# 8_RK3399_SDIO_SPI_GPIOs.net
KiCad netlist of a schematic drawn in Altium Designer
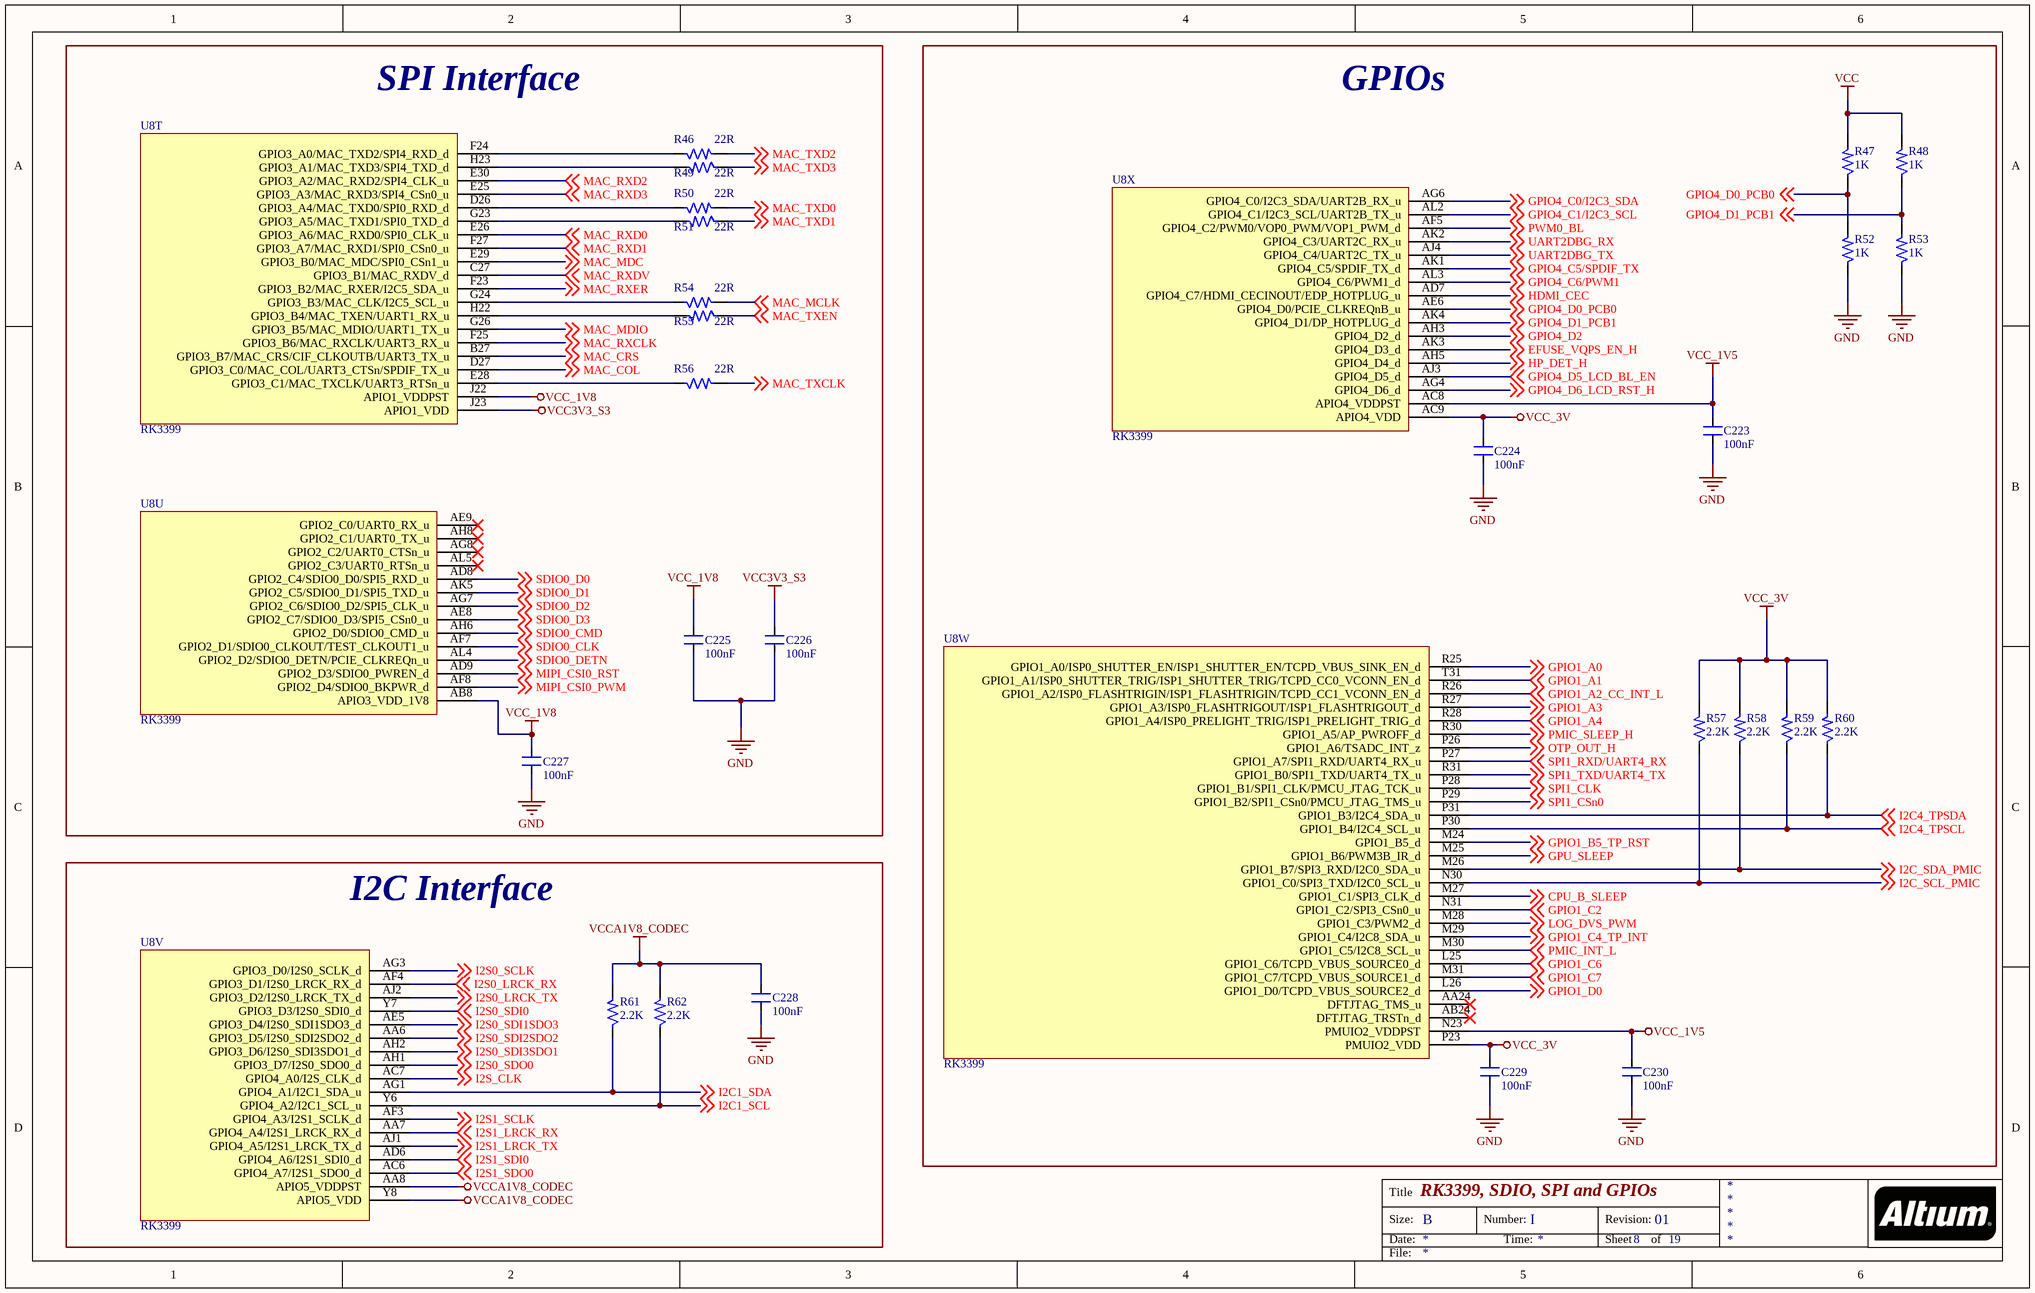
[diagram p0: [8] RK3399_SDIO_SPI_GPIOs.SchDoc]

(export (version "E")
  (design (tool "Eeschema 10.0.6"))
  (components
    (comp (ref "C223")
      (value "100nF")
      (footprint "CAP_0201")
      (description "0.1µF ±10% 25V Ceramic Capacitor X5R 0201 (0603 Metric)")
      (fields
        (field (name "MANUFACTURER") "TDK Corporation")
        (field (name "MANUFACTURER PART NUMBER") "C0603X5R1E104K030BB")
      )
      (libsource (lib "EsteemPCB_SOM_Course_intlib") (part "CAP_100nF-25V-10%-0201"))
    )
    (comp (ref "C224")
      (value "100nF")
      (footprint "CAP_0201")
      (description "0.1µF ±10% 25V Ceramic Capacitor X5R 0201 (0603 Metric)")
      (fields
        (field (name "MANUFACTURER") "TDK Corporation")
        (field (name "MANUFACTURER PART NUMBER") "C0603X5R1E104K030BB")
      )
      (libsource (lib "EsteemPCB_SOM_Course_intlib") (part "CAP_100nF-25V-10%-0201"))
    )
    (comp (ref "C225")
      (value "100nF")
      (footprint "CAP_0201")
      (description "0.1µF ±10% 25V Ceramic Capacitor X5R 0201 (0603 Metric)")
      (fields
        (field (name "MANUFACTURER") "TDK Corporation")
        (field (name "MANUFACTURER PART NUMBER") "C0603X5R1E104K030BB")
      )
      (libsource (lib "EsteemPCB_SOM_Course_intlib") (part "CAP_100nF-25V-10%-0201"))
    )
    (comp (ref "C226")
      (value "100nF")
      (footprint "CAP_0201")
      (description "0.1µF ±10% 25V Ceramic Capacitor X5R 0201 (0603 Metric)")
      (fields
        (field (name "MANUFACTURER") "TDK Corporation")
        (field (name "MANUFACTURER PART NUMBER") "C0603X5R1E104K030BB")
      )
      (libsource (lib "EsteemPCB_SOM_Course_intlib") (part "CAP_100nF-25V-10%-0201"))
    )
    (comp (ref "C227")
      (value "100nF")
      (footprint "CAP_0201")
      (description "0.1µF ±10% 25V Ceramic Capacitor X5R 0201 (0603 Metric)")
      (fields
        (field (name "MANUFACTURER") "TDK Corporation")
        (field (name "MANUFACTURER PART NUMBER") "C0603X5R1E104K030BB")
      )
      (libsource (lib "EsteemPCB_SOM_Course_intlib") (part "CAP_100nF-25V-10%-0201"))
    )
    (comp (ref "C228")
      (value "100nF")
      (footprint "CAP_0201")
      (description "0.1µF ±10% 25V Ceramic Capacitor X5R 0201 (0603 Metric)")
      (fields
        (field (name "MANUFACTURER") "TDK Corporation")
        (field (name "MANUFACTURER PART NUMBER") "C0603X5R1E104K030BB")
      )
      (libsource (lib "EsteemPCB_SOM_Course_intlib") (part "CAP_100nF-25V-10%-0201"))
    )
    (comp (ref "C229")
      (value "100nF")
      (footprint "CAP_0201")
      (description "0.1µF ±10% 25V Ceramic Capacitor X5R 0201 (0603 Metric)")
      (fields
        (field (name "MANUFACTURER") "TDK Corporation")
        (field (name "MANUFACTURER PART NUMBER") "C0603X5R1E104K030BB")
      )
      (libsource (lib "EsteemPCB_SOM_Course_intlib") (part "CAP_100nF-25V-10%-0201"))
    )
    (comp (ref "C230")
      (value "100nF")
      (footprint "CAP_0201")
      (description "0.1µF ±10% 25V Ceramic Capacitor X5R 0201 (0603 Metric)")
      (fields
        (field (name "MANUFACTURER") "TDK Corporation")
        (field (name "MANUFACTURER PART NUMBER") "C0603X5R1E104K030BB")
      )
      (libsource (lib "EsteemPCB_SOM_Course_intlib") (part "CAP_100nF-25V-10%-0201"))
    )
    (comp (ref "R46")
      (value "22R")
      (footprint "RES_0201")
      (description "22 Ohms ±1% 0.05W, 1/20W Chip Resistor 0201 (0603 Metric) Moisture Resistant Thick Film")
      (fields
        (field (name "MANUFACTURER") "Yageo")
        (field (name "MANUFACTURER PART NUMBER") "RC0201FR-0722RL")
      )
      (libsource (lib "EsteemPCB_SOM_Course_intlib") (part "RES_22R-0.05W-1%-0201"))
    )
    (comp (ref "R47")
      (value "1K")
      (footprint "RES_0201")
      (description "1 kOhms ±1% 0.05W, 1/20W Chip Resistor 0201 (0603 Metric) Thick Film")
      (fields
        (field (name "MANUFACTURER") "Yageo")
        (field (name "MANUFACTURER PART NUMBER") "RC0201FR-071KL")
      )
      (libsource (lib "EsteemPCB_SOM_Course_intlib") (part "RES_1K-0.05W-1%-0201"))
    )
    (comp (ref "R48")
      (value "1K")
      (footprint "RES_0201")
      (description "1 kOhms ±1% 0.05W, 1/20W Chip Resistor 0201 (0603 Metric) Thick Film")
      (fields
        (field (name "MANUFACTURER") "Yageo")
        (field (name "MANUFACTURER PART NUMBER") "RC0201FR-071KL")
      )
      (libsource (lib "EsteemPCB_SOM_Course_intlib") (part "RES_1K-0.05W-1%-0201"))
    )
    (comp (ref "R49")
      (value "22R")
      (footprint "RES_0201")
      (description "22 Ohms ±1% 0.05W, 1/20W Chip Resistor 0201 (0603 Metric) Moisture Resistant Thick Film")
      (fields
        (field (name "MANUFACTURER") "Yageo")
        (field (name "MANUFACTURER PART NUMBER") "RC0201FR-0722RL")
      )
      (libsource (lib "EsteemPCB_SOM_Course_intlib") (part "RES_22R-0.05W-1%-0201"))
    )
    (comp (ref "R50")
      (value "22R")
      (footprint "RES_0201")
      (description "22 Ohms ±1% 0.05W, 1/20W Chip Resistor 0201 (0603 Metric) Moisture Resistant Thick Film")
      (fields
        (field (name "MANUFACTURER") "Yageo")
        (field (name "MANUFACTURER PART NUMBER") "RC0201FR-0722RL")
      )
      (libsource (lib "EsteemPCB_SOM_Course_intlib") (part "RES_22R-0.05W-1%-0201"))
    )
    (comp (ref "R51")
      (value "22R")
      (footprint "RES_0201")
      (description "22 Ohms ±1% 0.05W, 1/20W Chip Resistor 0201 (0603 Metric) Moisture Resistant Thick Film")
      (fields
        (field (name "MANUFACTURER") "Yageo")
        (field (name "MANUFACTURER PART NUMBER") "RC0201FR-0722RL")
      )
      (libsource (lib "EsteemPCB_SOM_Course_intlib") (part "RES_22R-0.05W-1%-0201"))
    )
    (comp (ref "R52")
      (value "1K")
      (footprint "RES_0402")
      (description "1 kOhms ±1% 0.1W, 1/10W Chip Resistor 0402 (1005 Metric) Anti-Sulfur Thin Film")
      (fields
        (field (name "MANUFACTURER") "Vishay Beyschlag/Draloric/BC Components")
        (field (name "MANUFACTURER PART NUMBER") "MCS04020C1001FE000")
      )
      (libsource (lib "EsteemPCB_SOM_Course_intlib") (part "RES_1K-0.1W-1%-0402"))
    )
    (comp (ref "R53")
      (value "1K")
      (footprint "RES_0402")
      (description "1 kOhms ±1% 0.1W, 1/10W Chip Resistor 0402 (1005 Metric) Anti-Sulfur Thin Film")
      (fields
        (field (name "MANUFACTURER") "Vishay Beyschlag/Draloric/BC Components")
        (field (name "MANUFACTURER PART NUMBER") "MCS04020C1001FE000")
      )
      (libsource (lib "EsteemPCB_SOM_Course_intlib") (part "RES_1K-0.1W-1%-0402"))
    )
    (comp (ref "R54")
      (value "22R")
      (footprint "RES_0201")
      (description "22 Ohms ±1% 0.05W, 1/20W Chip Resistor 0201 (0603 Metric) Moisture Resistant Thick Film")
      (fields
        (field (name "MANUFACTURER") "Yageo")
        (field (name "MANUFACTURER PART NUMBER") "RC0201FR-0722RL")
      )
      (libsource (lib "EsteemPCB_SOM_Course_intlib") (part "RES_22R-0.05W-1%-0201"))
    )
    (comp (ref "R55")
      (value "22R")
      (footprint "RES_0201")
      (description "22 Ohms ±1% 0.05W, 1/20W Chip Resistor 0201 (0603 Metric) Moisture Resistant Thick Film")
      (fields
        (field (name "MANUFACTURER") "Yageo")
        (field (name "MANUFACTURER PART NUMBER") "RC0201FR-0722RL")
      )
      (libsource (lib "EsteemPCB_SOM_Course_intlib") (part "RES_22R-0.05W-1%-0201"))
    )
    (comp (ref "R56")
      (value "22R")
      (footprint "RES_0201")
      (description "22 Ohms ±1% 0.05W, 1/20W Chip Resistor 0201 (0603 Metric) Moisture Resistant Thick Film")
      (fields
        (field (name "MANUFACTURER") "Yageo")
        (field (name "MANUFACTURER PART NUMBER") "RC0201FR-0722RL")
      )
      (libsource (lib "EsteemPCB_SOM_Course_intlib") (part "RES_22R-0.05W-1%-0201"))
    )
    (comp (ref "R57")
      (value "2.2K")
      (footprint "RES_0201")
      (description "2.2 kOhms ±1% 0.05W, 1/20W Chip Resistor 0201 (0603 Metric) Thick Film")
      (fields
        (field (name "MANUFACTURER") "Stackpole Electronics Inc")
        (field (name "MANUFACTURER PART NUMBER") "RMCF0201FT2K20")
      )
      (libsource (lib "EsteemPCB_SOM_Course_intlib") (part "RES_2.2K-0.05W-1%-0201"))
    )
    (comp (ref "R58")
      (value "2.2K")
      (footprint "RES_0201")
      (description "2.2 kOhms ±1% 0.05W, 1/20W Chip Resistor 0201 (0603 Metric) Thick Film")
      (fields
        (field (name "MANUFACTURER") "Stackpole Electronics Inc")
        (field (name "MANUFACTURER PART NUMBER") "RMCF0201FT2K20")
      )
      (libsource (lib "EsteemPCB_SOM_Course_intlib") (part "RES_2.2K-0.05W-1%-0201"))
    )
    (comp (ref "R59")
      (value "2.2K")
      (footprint "RES_0201")
      (description "2.2 kOhms ±1% 0.05W, 1/20W Chip Resistor 0201 (0603 Metric) Thick Film")
      (fields
        (field (name "MANUFACTURER") "Stackpole Electronics Inc")
        (field (name "MANUFACTURER PART NUMBER") "RMCF0201FT2K20")
      )
      (libsource (lib "EsteemPCB_SOM_Course_intlib") (part "RES_2.2K-0.05W-1%-0201"))
    )
    (comp (ref "R60")
      (value "2.2K")
      (footprint "RES_0201")
      (description "2.2 kOhms ±1% 0.05W, 1/20W Chip Resistor 0201 (0603 Metric) Thick Film")
      (fields
        (field (name "MANUFACTURER") "Stackpole Electronics Inc")
        (field (name "MANUFACTURER PART NUMBER") "RMCF0201FT2K20")
      )
      (libsource (lib "EsteemPCB_SOM_Course_intlib") (part "RES_2.2K-0.05W-1%-0201"))
    )
    (comp (ref "R61")
      (value "2.2K")
      (footprint "RES_0201")
      (description "2.2 kOhms ±1% 0.05W, 1/20W Chip Resistor 0201 (0603 Metric) Thick Film")
      (fields
        (field (name "MANUFACTURER") "Stackpole Electronics Inc")
        (field (name "MANUFACTURER PART NUMBER") "RMCF0201FT2K20")
      )
      (libsource (lib "EsteemPCB_SOM_Course_intlib") (part "RES_2.2K-0.05W-1%-0201"))
    )
    (comp (ref "R62")
      (value "2.2K")
      (footprint "RES_0201")
      (description "2.2 kOhms ±1% 0.05W, 1/20W Chip Resistor 0201 (0603 Metric) Thick Film")
      (fields
        (field (name "MANUFACTURER") "Stackpole Electronics Inc")
        (field (name "MANUFACTURER PART NUMBER") "RMCF0201FT2K20")
      )
      (libsource (lib "EsteemPCB_SOM_Course_intlib") (part "RES_2.2K-0.05W-1%-0201"))
    )
    (comp (ref "U8")
      (value "RK3399")
      (footprint "FBGA828_23_826X826")
      (description "RK3399 is a low power, high performance processor for computing, personal mobile.")
      (fields (field (name "MANUFACTURER") "Rockchip"))
      (libsource (lib "EsteemPCB_SOM_Course_intlib") (part "IC_RK3399-FCBGA828"))
    )
  )
  (nets
    (net (code "1") (name "CPU_B_SLEEP") (class "Default")
      (node (ref "U8") (pin "M27") (pinfunction "GPIO1_C1/SPI3_CLK_d_M27") (pintype "passive"))
    )
    (net (code "2") (name "EFUSE_VQPS_EN_H") (class "Default")
      (node (ref "U8") (pin "AK3") (pinfunction "GPIO4_D3_d_AK3") (pintype "passive"))
    )
    (net (code "3") (name "GND") (class "Default")
      (node (ref "C223") (pin "1") (pinfunction "1_1") (pintype "passive"))
      (node (ref "C224") (pin "1") (pinfunction "1_1") (pintype "passive"))
      (node (ref "C225") (pin "1") (pinfunction "1_1") (pintype "passive"))
      (node (ref "C226") (pin "1") (pinfunction "1_1") (pintype "passive"))
      (node (ref "C227") (pin "1") (pinfunction "1_1") (pintype "passive"))
      (node (ref "C228") (pin "1") (pinfunction "1_1") (pintype "passive"))
      (node (ref "C229") (pin "1") (pinfunction "1_1") (pintype "passive"))
      (node (ref "C230") (pin "1") (pinfunction "1_1") (pintype "passive"))
      (node (ref "R52") (pin "1") (pinfunction "1_1") (pintype "passive"))
      (node (ref "R53") (pin "1") (pinfunction "1_1") (pintype "passive"))
    )
    (net (code "4") (name "GPIO1_A0") (class "Default")
      (node (ref "U8") (pin "R25") (pinfunction "GPIO1_A0/ISP0_SHUTTER_EN/ISP1_SHUTTER_EN/TCPD_VBUS_SINK_EN_d_R25") (pintype "passive"))
    )
    (net (code "5") (name "GPIO1_A1") (class "Default")
      (node (ref "U8") (pin "T31") (pinfunction "GPIO1_A1/ISP0_SHUTTER_TRIG/ISP1_SHUTTER_TRIG/TCPD_CC0_VCONN_EN_d_T31") (pintype "passive"))
    )
    (net (code "6") (name "GPIO1_A2_CC_INT_L") (class "Default")
      (node (ref "U8") (pin "R26") (pinfunction "GPIO1_A2/ISP0_FLASHTRIGIN/ISP1_FLASHTRIGIN/TCPD_CC1_VCONN_EN_d_R26") (pintype "passive"))
    )
    (net (code "7") (name "GPIO1_A3") (class "Default")
      (node (ref "U8") (pin "R27") (pinfunction "GPIO1_A3/ISP0_FLASHTRIGOUT/ISP1_FLASHTRIGOUT_d_R27") (pintype "passive"))
    )
    (net (code "8") (name "GPIO1_A4") (class "Default")
      (node (ref "U8") (pin "R28") (pinfunction "GPIO1_A4/ISP0_PRELIGHT_TRIG/ISP1_PRELIGHT_TRIG_d_R28") (pintype "passive"))
    )
    (net (code "9") (name "GPIO1_B5_TP_RST") (class "Default")
      (node (ref "U8") (pin "M24") (pinfunction "GPIO1_B5_d_M24") (pintype "passive"))
    )
    (net (code "10") (name "GPIO1_C2") (class "Default")
      (node (ref "U8") (pin "N31") (pinfunction "GPIO1_C2/SPI3_CSn0_u_N31") (pintype "passive"))
    )
    (net (code "11") (name "GPIO1_C4_TP_INT") (class "Default")
      (node (ref "U8") (pin "M29") (pinfunction "GPIO1_C4/I2C8_SDA_u_M29") (pintype "passive"))
    )
    (net (code "12") (name "GPIO1_C6") (class "Default")
      (node (ref "U8") (pin "L25") (pinfunction "GPIO1_C6/TCPD_VBUS_SOURCE0_d_L25") (pintype "passive"))
    )
    (net (code "13") (name "GPIO1_C7") (class "Default")
      (node (ref "U8") (pin "M31") (pinfunction "GPIO1_C7/TCPD_VBUS_SOURCE1_d_M31") (pintype "passive"))
    )
    (net (code "14") (name "GPIO1_D0") (class "Default")
      (node (ref "U8") (pin "L26") (pinfunction "GPIO1_D0/TCPD_VBUS_SOURCE2_d_L26") (pintype "passive"))
    )
    (net (code "15") (name "GPIO4_C0{slash}I2C3_SDA") (class "Default")
      (node (ref "U8") (pin "AG6") (pinfunction "GPIO4_C0/I2C3_SDA/UART2B_RX_u_AG6") (pintype "passive"))
    )
    (net (code "16") (name "GPIO4_C1{slash}I2C3_SCL") (class "Default")
      (node (ref "U8") (pin "AL2") (pinfunction "GPIO4_C1/I2C3_SCL/UART2B_TX_u_AL2") (pintype "passive"))
    )
    (net (code "17") (name "GPIO4_C5{slash}SPDIF_TX") (class "Default")
      (node (ref "U8") (pin "AK1") (pinfunction "GPIO4_C5/SPDIF_TX_d_AK1") (pintype "passive"))
    )
    (net (code "18") (name "GPIO4_C6{slash}PWM1") (class "Default")
      (node (ref "U8") (pin "AL3") (pinfunction "GPIO4_C6/PWM1_d_AL3") (pintype "passive"))
    )
    (net (code "19") (name "GPIO4_D0_PCB0") (class "Default")
      (node (ref "R47") (pin "1") (pinfunction "1_1") (pintype "passive"))
      (node (ref "R52") (pin "2") (pinfunction "2_2") (pintype "passive"))
      (node (ref "U8") (pin "AE6") (pinfunction "GPIO4_D0/PCIE_CLKREQnB_u_AE6") (pintype "passive"))
    )
    (net (code "20") (name "GPIO4_D1_PCB1") (class "Default")
      (node (ref "R48") (pin "1") (pinfunction "1_1") (pintype "passive"))
      (node (ref "R53") (pin "2") (pinfunction "2_2") (pintype "passive"))
      (node (ref "U8") (pin "AK4") (pinfunction "GPIO4_D1/DP_HOTPLUG_d_AK4") (pintype "passive"))
    )
    (net (code "21") (name "GPIO4_D2") (class "Default")
      (node (ref "U8") (pin "AH3") (pinfunction "GPIO4_D2_d_AH3") (pintype "passive"))
    )
    (net (code "22") (name "GPIO4_D5_LCD_BL_EN") (class "Default")
      (node (ref "U8") (pin "AJ3") (pinfunction "GPIO4_D5_d_AJ3") (pintype "passive"))
    )
    (net (code "23") (name "GPIO4_D6_LCD_RST_H") (class "Default")
      (node (ref "U8") (pin "AG4") (pinfunction "GPIO4_D6_d_AG4") (pintype "passive"))
    )
    (net (code "24") (name "GPU_SLEEP") (class "Default")
      (node (ref "U8") (pin "M25") (pinfunction "GPIO1_B6/PWM3B_IR_d_M25") (pintype "passive"))
    )
    (net (code "25") (name "HDMI_CEC") (class "Default")
      (node (ref "U8") (pin "AD7") (pinfunction "GPIO4_C7/HDMI_CECINOUT/EDP_HOTPLUG_u_AD7") (pintype "passive"))
    )
    (net (code "26") (name "HP_DET_H") (class "Default")
      (node (ref "U8") (pin "AH5") (pinfunction "GPIO4_D4_d_AH5") (pintype "passive"))
    )
    (net (code "27") (name "I2C1_SCL") (class "Default")
      (node (ref "R62") (pin "1") (pinfunction "1_1") (pintype "passive"))
      (node (ref "U8") (pin "Y6") (pinfunction "GPIO4_A2/I2C1_SCL_u_Y6") (pintype "passive"))
    )
    (net (code "28") (name "I2C1_SDA") (class "Default")
      (node (ref "R61") (pin "1") (pinfunction "1_1") (pintype "passive"))
      (node (ref "U8") (pin "AG1") (pinfunction "GPIO4_A1/I2C1_SDA_u_AG1") (pintype "passive"))
    )
    (net (code "29") (name "I2C4_TPSCL") (class "Default")
      (node (ref "R59") (pin "1") (pinfunction "1_1") (pintype "passive"))
      (node (ref "U8") (pin "P30") (pinfunction "GPIO1_B4/I2C4_SCL_u_P30") (pintype "passive"))
    )
    (net (code "30") (name "I2C4_TPSDA") (class "Default")
      (node (ref "R60") (pin "1") (pinfunction "1_1") (pintype "passive"))
      (node (ref "U8") (pin "P31") (pinfunction "GPIO1_B3/I2C4_SDA_u_P31") (pintype "passive"))
    )
    (net (code "31") (name "I2C_SCL_PMIC") (class "Default")
      (node (ref "R57") (pin "1") (pinfunction "1_1") (pintype "passive"))
      (node (ref "U8") (pin "N30") (pinfunction "GPIO1_C0/SPI3_TXD/I2C0_SCL_u_N30") (pintype "passive"))
    )
    (net (code "32") (name "I2C_SDA_PMIC") (class "Default")
      (node (ref "R58") (pin "1") (pinfunction "1_1") (pintype "passive"))
      (node (ref "U8") (pin "M26") (pinfunction "GPIO1_B7/SPI3_RXD/I2C0_SDA_u_M26") (pintype "passive"))
    )
    (net (code "33") (name "I2S0_LRCK_RX") (class "Default")
      (node (ref "U8") (pin "AF4") (pinfunction "GPIO3_D1/I2S0_LRCK_RX_d_AF4") (pintype "passive"))
    )
    (net (code "34") (name "I2S0_LRCK_TX") (class "Default")
      (node (ref "U8") (pin "AJ2") (pinfunction "GPIO3_D2/I2S0_LRCK_TX_d_AJ2") (pintype "passive"))
    )
    (net (code "35") (name "I2S0_SCLK") (class "Default")
      (node (ref "U8") (pin "AG3") (pinfunction "GPIO3_D0/I2S0_SCLK_d_AG3") (pintype "passive"))
    )
    (net (code "36") (name "I2S0_SDI0") (class "Default")
      (node (ref "U8") (pin "Y7") (pinfunction "GPIO3_D3/I2S0_SDI0_d_Y7") (pintype "passive"))
    )
    (net (code "37") (name "I2S0_SDI1SDO3") (class "Default")
      (node (ref "U8") (pin "AE5") (pinfunction "GPIO3_D4/I2S0_SDI1SDO3_d_AE5") (pintype "passive"))
    )
    (net (code "38") (name "I2S0_SDI2SDO2") (class "Default")
      (node (ref "U8") (pin "AA6") (pinfunction "GPIO3_D5/I2S0_SDI2SDO2_d_AA6") (pintype "passive"))
    )
    (net (code "39") (name "I2S0_SDI3SDO1") (class "Default")
      (node (ref "U8") (pin "AH2") (pinfunction "GPIO3_D6/I2S0_SDI3SDO1_d_AH2") (pintype "passive"))
    )
    (net (code "40") (name "I2S0_SDO0") (class "Default")
      (node (ref "U8") (pin "AH1") (pinfunction "GPIO3_D7/I2S0_SDO0_d_AH1") (pintype "passive"))
    )
    (net (code "41") (name "I2S1_LRCK_RX") (class "Default")
      (node (ref "U8") (pin "AA7") (pinfunction "GPIO4_A4/I2S1_LRCK_RX_d_AA7") (pintype "passive"))
    )
    (net (code "42") (name "I2S1_LRCK_TX") (class "Default")
      (node (ref "U8") (pin "AJ1") (pinfunction "GPIO4_A5/I2S1_LRCK_TX_d_AJ1") (pintype "passive"))
    )
    (net (code "43") (name "I2S1_SCLK") (class "Default")
      (node (ref "U8") (pin "AF3") (pinfunction "GPIO4_A3/I2S1_SCLK_d_AF3") (pintype "passive"))
    )
    (net (code "44") (name "I2S1_SDI0") (class "Default")
      (node (ref "U8") (pin "AD6") (pinfunction "GPIO4_A6/I2S1_SDI0_d_AD6") (pintype "passive"))
    )
    (net (code "45") (name "I2S1_SDO0") (class "Default")
      (node (ref "U8") (pin "AC6") (pinfunction "GPIO4_A7/I2S1_SDO0_d_AC6") (pintype "passive"))
    )
    (net (code "46") (name "I2S_CLK") (class "Default")
      (node (ref "U8") (pin "AC7") (pinfunction "GPIO4_A0/I2S_CLK_d_AC7") (pintype "passive"))
    )
    (net (code "47") (name "LOG_DVS_PWM") (class "Default")
      (node (ref "U8") (pin "M28") (pinfunction "GPIO1_C3/PWM2_d_M28") (pintype "passive"))
    )
    (net (code "48") (name "MAC_COL") (class "Default")
      (node (ref "U8") (pin "D27") (pinfunction "GPIO3_C0/MAC_COL/UART3_CTSn/SPDIF_TX_u_D27") (pintype "passive"))
    )
    (net (code "49") (name "MAC_CRS") (class "Default")
      (node (ref "U8") (pin "B27") (pinfunction "GPIO3_B7/MAC_CRS/CIF_CLKOUTB/UART3_TX_u_B27") (pintype "passive"))
    )
    (net (code "50") (name "MAC_MCLK") (class "Default")
      (node (ref "R54") (pin "2") (pinfunction "2_2") (pintype "passive"))
    )
    (net (code "51") (name "MAC_MDC") (class "Default")
      (node (ref "U8") (pin "E29") (pinfunction "GPIO3_B0/MAC_MDC/SPI0_CSn1_u_E29") (pintype "passive"))
    )
    (net (code "52") (name "MAC_MDIO") (class "Default")
      (node (ref "U8") (pin "G26") (pinfunction "GPIO3_B5/MAC_MDIO/UART1_TX_u_G26") (pintype "passive"))
    )
    (net (code "53") (name "MAC_RXCLK") (class "Default")
      (node (ref "U8") (pin "F25") (pinfunction "GPIO3_B6/MAC_RXCLK/UART3_RX_u_F25") (pintype "passive"))
    )
    (net (code "54") (name "MAC_RXD0") (class "Default")
      (node (ref "U8") (pin "E26") (pinfunction "GPIO3_A6/MAC_RXD0/SPI0_CLK_u_E26") (pintype "passive"))
    )
    (net (code "55") (name "MAC_RXD1") (class "Default")
      (node (ref "U8") (pin "F27") (pinfunction "GPIO3_A7/MAC_RXD1/SPI0_CSn0_u_F27") (pintype "passive"))
    )
    (net (code "56") (name "MAC_RXD2") (class "Default")
      (node (ref "U8") (pin "E30") (pinfunction "GPIO3_A2/MAC_RXD2/SPI4_CLK_u_E30") (pintype "passive"))
    )
    (net (code "57") (name "MAC_RXD3") (class "Default")
      (node (ref "U8") (pin "E25") (pinfunction "GPIO3_A3/MAC_RXD3/SPI4_CSn0_u_E25") (pintype "passive"))
    )
    (net (code "58") (name "MAC_RXDV") (class "Default")
      (node (ref "U8") (pin "C27") (pinfunction "GPIO3_B1/MAC_RXDV_d_C27") (pintype "passive"))
    )
    (net (code "59") (name "MAC_RXER") (class "Default")
      (node (ref "U8") (pin "F23") (pinfunction "GPIO3_B2/MAC_RXER/I2C5_SDA_u_F23") (pintype "passive"))
    )
    (net (code "60") (name "MAC_TXCLK") (class "Default")
      (node (ref "R56") (pin "2") (pinfunction "2_2") (pintype "passive"))
    )
    (net (code "61") (name "MAC_TXD0") (class "Default")
      (node (ref "R50") (pin "2") (pinfunction "2_2") (pintype "passive"))
    )
    (net (code "62") (name "MAC_TXD1") (class "Default")
      (node (ref "R51") (pin "1") (pinfunction "1_1") (pintype "passive"))
    )
    (net (code "63") (name "MAC_TXD2") (class "Default")
      (node (ref "R46") (pin "2") (pinfunction "2_2") (pintype "passive"))
    )
    (net (code "64") (name "MAC_TXD3") (class "Default")
      (node (ref "R49") (pin "1") (pinfunction "1_1") (pintype "passive"))
    )
    (net (code "65") (name "MAC_TXEN") (class "Default")
      (node (ref "R55") (pin "1") (pinfunction "1_1") (pintype "passive"))
    )
    (net (code "66") (name "MIPI_CSI0_PWM") (class "Default")
      (node (ref "U8") (pin "AF8") (pinfunction "GPIO2_D4/SDIO0_BKPWR_d_AF8") (pintype "passive"))
    )
    (net (code "67") (name "MIPI_CSI0_RST") (class "Default")
      (node (ref "U8") (pin "AD9") (pinfunction "GPIO2_D3/SDIO0_PWREN_d_AD9") (pintype "passive"))
    )
    (net (code "68") (name "Net-(U8T-GPIO3_A0{slash}MAC_TXD2{slash}SPI4_RXD_d)") (class "Default")
      (node (ref "R46") (pin "1") (pinfunction "1_1") (pintype "passive"))
      (node (ref "U8") (pin "F24") (pinfunction "GPIO3_A0/MAC_TXD2/SPI4_RXD_d_F24") (pintype "passive"))
    )
    (net (code "69") (name "Net-(U8T-GPIO3_A1{slash}MAC_TXD3{slash}SPI4_TXD_d)") (class "Default")
      (node (ref "R49") (pin "2") (pinfunction "2_2") (pintype "passive"))
      (node (ref "U8") (pin "H23") (pinfunction "GPIO3_A1/MAC_TXD3/SPI4_TXD_d_H23") (pintype "passive"))
    )
    (net (code "70") (name "Net-(U8T-GPIO3_A4{slash}MAC_TXD0{slash}SPI0_RXD_d)") (class "Default")
      (node (ref "R50") (pin "1") (pinfunction "1_1") (pintype "passive"))
      (node (ref "U8") (pin "D26") (pinfunction "GPIO3_A4/MAC_TXD0/SPI0_RXD_d_D26") (pintype "passive"))
    )
    (net (code "71") (name "Net-(U8T-GPIO3_A5{slash}MAC_TXD1{slash}SPI0_TXD_d)") (class "Default")
      (node (ref "R51") (pin "2") (pinfunction "2_2") (pintype "passive"))
      (node (ref "U8") (pin "G23") (pinfunction "GPIO3_A5/MAC_TXD1/SPI0_TXD_d_G23") (pintype "passive"))
    )
    (net (code "72") (name "Net-(U8T-GPIO3_B3{slash}MAC_CLK{slash}I2C5_SCL_u)") (class "Default")
      (node (ref "R54") (pin "1") (pinfunction "1_1") (pintype "passive"))
      (node (ref "U8") (pin "G24") (pinfunction "GPIO3_B3/MAC_CLK/I2C5_SCL_u_G24") (pintype "passive"))
    )
    (net (code "73") (name "Net-(U8T-GPIO3_B4{slash}MAC_TXEN{slash}UART1_RX_u)") (class "Default")
      (node (ref "R55") (pin "2") (pinfunction "2_2") (pintype "passive"))
      (node (ref "U8") (pin "H22") (pinfunction "GPIO3_B4/MAC_TXEN/UART1_RX_u_H22") (pintype "passive"))
    )
    (net (code "74") (name "Net-(U8T-GPIO3_C1{slash}MAC_TXCLK{slash}UART3_RTSn_u)") (class "Default")
      (node (ref "R56") (pin "1") (pinfunction "1_1") (pintype "passive"))
      (node (ref "U8") (pin "E28") (pinfunction "GPIO3_C1/MAC_TXCLK/UART3_RTSn_u_E28") (pintype "passive"))
    )
    (net (code "75") (name "OTP_OUT_H") (class "Default")
      (node (ref "U8") (pin "P26") (pinfunction "GPIO1_A6/TSADC_INT_z_P26") (pintype "passive"))
    )
    (net (code "76") (name "PMIC_INT_L") (class "Default")
      (node (ref "U8") (pin "M30") (pinfunction "GPIO1_C5/I2C8_SCL_u_M30") (pintype "passive"))
    )
    (net (code "77") (name "PMIC_SLEEP_H") (class "Default")
      (node (ref "U8") (pin "R30") (pinfunction "GPIO1_A5/AP_PWROFF_d_R30") (pintype "passive"))
    )
    (net (code "78") (name "PWM0_BL") (class "Default")
      (node (ref "U8") (pin "AF5") (pinfunction "GPIO4_C2/PWM0/VOP0_PWM/VOP1_PWM_d_AF5") (pintype "passive"))
    )
    (net (code "79") (name "SDIO0_CLK") (class "Default")
      (node (ref "U8") (pin "AF7") (pinfunction "GPIO2_D1/SDIO0_CLKOUT/TEST_CLKOUT1_u_AF7") (pintype "passive"))
    )
    (net (code "80") (name "SDIO0_CMD") (class "Default")
      (node (ref "U8") (pin "AH6") (pinfunction "GPIO2_D0/SDIO0_CMD_u_AH6") (pintype "passive"))
    )
    (net (code "81") (name "SDIO0_D0") (class "Default")
      (node (ref "U8") (pin "AD8") (pinfunction "GPIO2_C4/SDIO0_D0/SPI5_RXD_u_AD8") (pintype "passive"))
    )
    (net (code "82") (name "SDIO0_D1") (class "Default")
      (node (ref "U8") (pin "AK5") (pinfunction "GPIO2_C5/SDIO0_D1/SPI5_TXD_u_AK5") (pintype "passive"))
    )
    (net (code "83") (name "SDIO0_D2") (class "Default")
      (node (ref "U8") (pin "AG7") (pinfunction "GPIO2_C6/SDIO0_D2/SPI5_CLK_u_AG7") (pintype "passive"))
    )
    (net (code "84") (name "SDIO0_D3") (class "Default")
      (node (ref "U8") (pin "AE8") (pinfunction "GPIO2_C7/SDIO0_D3/SPI5_CSn0_u_AE8") (pintype "passive"))
    )
    (net (code "85") (name "SDIO0_DETN") (class "Default")
      (node (ref "U8") (pin "AL4") (pinfunction "GPIO2_D2/SDIO0_DETN/PCIE_CLKREQn_u_AL4") (pintype "passive"))
    )
    (net (code "86") (name "SPI1_CLK") (class "Default")
      (node (ref "U8") (pin "P28") (pinfunction "GPIO1_B1/SPI1_CLK/PMCU_JTAG_TCK_u_P28") (pintype "passive"))
    )
    (net (code "87") (name "SPI1_CSn0") (class "Default")
      (node (ref "U8") (pin "P29") (pinfunction "GPIO1_B2/SPI1_CSn0/PMCU_JTAG_TMS_u_P29") (pintype "passive"))
    )
    (net (code "88") (name "SPI1_RXD{slash}UART4_RX") (class "Default")
      (node (ref "U8") (pin "P27") (pinfunction "GPIO1_A7/SPI1_RXD/UART4_RX_u_P27") (pintype "passive"))
    )
    (net (code "89") (name "SPI1_TXD{slash}UART4_TX") (class "Default")
      (node (ref "U8") (pin "R31") (pinfunction "GPIO1_B0/SPI1_TXD/UART4_TX_u_R31") (pintype "passive"))
    )
    (net (code "90") (name "UART2DBG_RX") (class "Default")
      (node (ref "U8") (pin "AK2") (pinfunction "GPIO4_C3/UART2C_RX_u_AK2") (pintype "passive"))
    )
    (net (code "91") (name "UART2DBG_TX") (class "Default")
      (node (ref "U8") (pin "AJ4") (pinfunction "GPIO4_C4/UART2C_TX_u_AJ4") (pintype "passive"))
    )
    (net (code "92") (name "VCC") (class "Default")
      (node (ref "R47") (pin "2") (pinfunction "2_2") (pintype "passive"))
      (node (ref "R48") (pin "2") (pinfunction "2_2") (pintype "passive"))
    )
    (net (code "93") (name "VCC3V3_S3") (class "Default")
      (node (ref "C226") (pin "2") (pinfunction "2_2") (pintype "passive"))
      (node (ref "U8") (pin "J23") (pinfunction "APIO1_VDD_J23") (pintype "passive"))
    )
    (net (code "94") (name "VCCA1V8_CODEC") (class "Default")
      (node (ref "C228") (pin "2") (pinfunction "2_2") (pintype "passive"))
      (node (ref "R61") (pin "2") (pinfunction "2_2") (pintype "passive"))
      (node (ref "R62") (pin "2") (pinfunction "2_2") (pintype "passive"))
      (node (ref "U8") (pin "AA8") (pinfunction "APIO5_VDDPST_AA8") (pintype "passive"))
      (node (ref "U8") (pin "Y8") (pinfunction "APIO5_VDD_Y8") (pintype "passive"))
    )
    (net (code "95") (name "VCC_1V5") (class "Default")
      (node (ref "C223") (pin "2") (pinfunction "2_2") (pintype "passive"))
      (node (ref "C230") (pin "2") (pinfunction "2_2") (pintype "passive"))
      (node (ref "U8") (pin "AC8") (pinfunction "APIO4_VDDPST_AC8") (pintype "passive"))
      (node (ref "U8") (pin "N23") (pinfunction "PMUIO2_VDDPST_N23") (pintype "passive"))
    )
    (net (code "96") (name "VCC_1V8") (class "Default")
      (node (ref "C225") (pin "2") (pinfunction "2_2") (pintype "passive"))
      (node (ref "C227") (pin "2") (pinfunction "2_2") (pintype "passive"))
      (node (ref "U8") (pin "AB8") (pinfunction "APIO3_VDD_1V8_AB8") (pintype "passive"))
      (node (ref "U8") (pin "J22") (pinfunction "APIO1_VDDPST_J22") (pintype "passive"))
    )
    (net (code "97") (name "VCC_3V") (class "Default")
      (node (ref "C224") (pin "2") (pinfunction "2_2") (pintype "passive"))
      (node (ref "C229") (pin "2") (pinfunction "2_2") (pintype "passive"))
      (node (ref "R57") (pin "2") (pinfunction "2_2") (pintype "passive"))
      (node (ref "R58") (pin "2") (pinfunction "2_2") (pintype "passive"))
      (node (ref "R59") (pin "2") (pinfunction "2_2") (pintype "passive"))
      (node (ref "R60") (pin "2") (pinfunction "2_2") (pintype "passive"))
      (node (ref "U8") (pin "AC9") (pinfunction "APIO4_VDD_AC9") (pintype "passive"))
      (node (ref "U8") (pin "P23") (pinfunction "PMUIO2_VDD_P23") (pintype "passive"))
    )
    (net (code "98") (name "unconnected-(U8U-GPIO2_C0{slash}UART0_RX_u-PadAE9)") (class "Default")
      (node (ref "U8") (pin "AE9") (pinfunction "GPIO2_C0/UART0_RX_u_AE9") (pintype "passive+no_connect"))
    )
    (net (code "99") (name "unconnected-(U8U-GPIO2_C1{slash}UART0_TX_u-PadAH8)") (class "Default")
      (node (ref "U8") (pin "AH8") (pinfunction "GPIO2_C1/UART0_TX_u_AH8") (pintype "passive+no_connect"))
    )
    (net (code "100") (name "unconnected-(U8U-GPIO2_C2{slash}UART0_CTSn_u-PadAG8)") (class "Default")
      (node (ref "U8") (pin "AG8") (pinfunction "GPIO2_C2/UART0_CTSn_u_AG8") (pintype "passive+no_connect"))
    )
    (net (code "101") (name "unconnected-(U8U-GPIO2_C3{slash}UART0_RTSn_u-PadAL5)") (class "Default")
      (node (ref "U8") (pin "AL5") (pinfunction "GPIO2_C3/UART0_RTSn_u_AL5") (pintype "passive+no_connect"))
    )
    (net (code "102") (name "unconnected-(U8W-DFTJTAG_TMS_u-PadAA24)") (class "Default")
      (node (ref "U8") (pin "AA24") (pinfunction "DFTJTAG_TMS_u_AA24") (pintype "passive+no_connect"))
    )
    (net (code "103") (name "unconnected-(U8W-DFTJTAG_TRSTn_d-PadAB24)") (class "Default")
      (node (ref "U8") (pin "AB24") (pinfunction "DFTJTAG_TRSTn_d_AB24") (pintype "passive+no_connect"))
    )
  )
)
